# CNC_LED.net
KiCad netlist of a schematic drawn in EAGLE
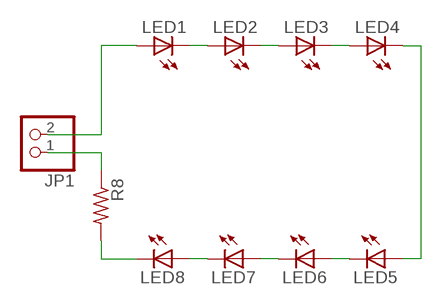
[diagram p0: schematic, sheet 1]

(export (version "E")
  (design (tool "Eeschema 10.0.6"))
  (components
    (comp (ref "JP1")
      (value "PINHD-1X2")
      (footprint "eagle-import:1X02")
      (libsource (lib "eagle-import") (part "PINHD-1X2"))
    )
    (comp (ref "LED1")
      (value "LEDCHIPLED_1206")
      (footprint "eagle-import:CHIPLED_1206")
      (libsource (lib "eagle-import") (part "LEDCHIPLED_1206"))
    )
    (comp (ref "LED2")
      (value "LEDCHIPLED_1206")
      (footprint "eagle-import:CHIPLED_1206")
      (libsource (lib "eagle-import") (part "LEDCHIPLED_1206"))
    )
    (comp (ref "LED3")
      (value "LEDCHIPLED_1206")
      (footprint "eagle-import:CHIPLED_1206")
      (libsource (lib "eagle-import") (part "LEDCHIPLED_1206"))
    )
    (comp (ref "LED4")
      (value "LEDCHIPLED_1206")
      (footprint "eagle-import:CHIPLED_1206")
      (libsource (lib "eagle-import") (part "LEDCHIPLED_1206"))
    )
    (comp (ref "LED5")
      (value "LEDCHIPLED_1206")
      (footprint "eagle-import:CHIPLED_1206")
      (libsource (lib "eagle-import") (part "LEDCHIPLED_1206"))
    )
    (comp (ref "LED6")
      (value "LEDCHIPLED_1206")
      (footprint "eagle-import:CHIPLED_1206")
      (libsource (lib "eagle-import") (part "LEDCHIPLED_1206"))
    )
    (comp (ref "LED7")
      (value "LEDCHIPLED_1206")
      (footprint "eagle-import:CHIPLED_1206")
      (libsource (lib "eagle-import") (part "LEDCHIPLED_1206"))
    )
    (comp (ref "LED8")
      (value "LEDCHIPLED_1206")
      (footprint "eagle-import:CHIPLED_1206")
      (libsource (lib "eagle-import") (part "LEDCHIPLED_1206"))
    )
    (comp (ref "R8")
      (value "R-US_R1206")
      (footprint "eagle-import:R1206")
      (libsource (lib "eagle-import") (part "R-US_R1206"))
    )
  )
  (nets
    (net (code "1") (name "Net-(JP1-Pad1)") (class "Default")
      (node (ref "JP1") (pin "1") (pinfunction "1_1") (pintype "passive"))
      (node (ref "R8") (pin "1") (pinfunction "1_1") (pintype "passive"))
    )
    (net (code "2") (name "Net-(JP1-Pad2)") (class "Default")
      (node (ref "JP1") (pin "2") (pinfunction "2_2") (pintype "passive"))
      (node (ref "LED1") (pin "A") (pinfunction "A_A") (pintype "passive"))
    )
    (net (code "3") (name "Net-(LED1-PadC)") (class "Default")
      (node (ref "LED1") (pin "C") (pinfunction "C_C") (pintype "passive"))
      (node (ref "LED2") (pin "A") (pinfunction "A_A") (pintype "passive"))
    )
    (net (code "4") (name "Net-(LED2-PadC)") (class "Default")
      (node (ref "LED2") (pin "C") (pinfunction "C_C") (pintype "passive"))
      (node (ref "LED3") (pin "A") (pinfunction "A_A") (pintype "passive"))
    )
    (net (code "5") (name "Net-(LED3-PadC)") (class "Default")
      (node (ref "LED3") (pin "C") (pinfunction "C_C") (pintype "passive"))
      (node (ref "LED4") (pin "A") (pinfunction "A_A") (pintype "passive"))
    )
    (net (code "6") (name "Net-(LED4-PadC)") (class "Default")
      (node (ref "LED4") (pin "C") (pinfunction "C_C") (pintype "passive"))
      (node (ref "LED5") (pin "A") (pinfunction "A_A") (pintype "passive"))
    )
    (net (code "7") (name "Net-(LED5-PadC)") (class "Default")
      (node (ref "LED5") (pin "C") (pinfunction "C_C") (pintype "passive"))
      (node (ref "LED6") (pin "A") (pinfunction "A_A") (pintype "passive"))
    )
    (net (code "8") (name "Net-(LED6-PadC)") (class "Default")
      (node (ref "LED6") (pin "C") (pinfunction "C_C") (pintype "passive"))
      (node (ref "LED7") (pin "A") (pinfunction "A_A") (pintype "passive"))
    )
    (net (code "9") (name "Net-(LED7-PadC)") (class "Default")
      (node (ref "LED7") (pin "C") (pinfunction "C_C") (pintype "passive"))
      (node (ref "LED8") (pin "A") (pinfunction "A_A") (pintype "passive"))
    )
    (net (code "10") (name "Net-(LED8-PadC)") (class "Default")
      (node (ref "LED8") (pin "C") (pinfunction "C_C") (pintype "passive"))
      (node (ref "R8") (pin "2") (pinfunction "2_2") (pintype "passive"))
    )
  )
)
